# SQUIDCtrl_Rev2.net
KiCad netlist of a schematic drawn in Altium Designer
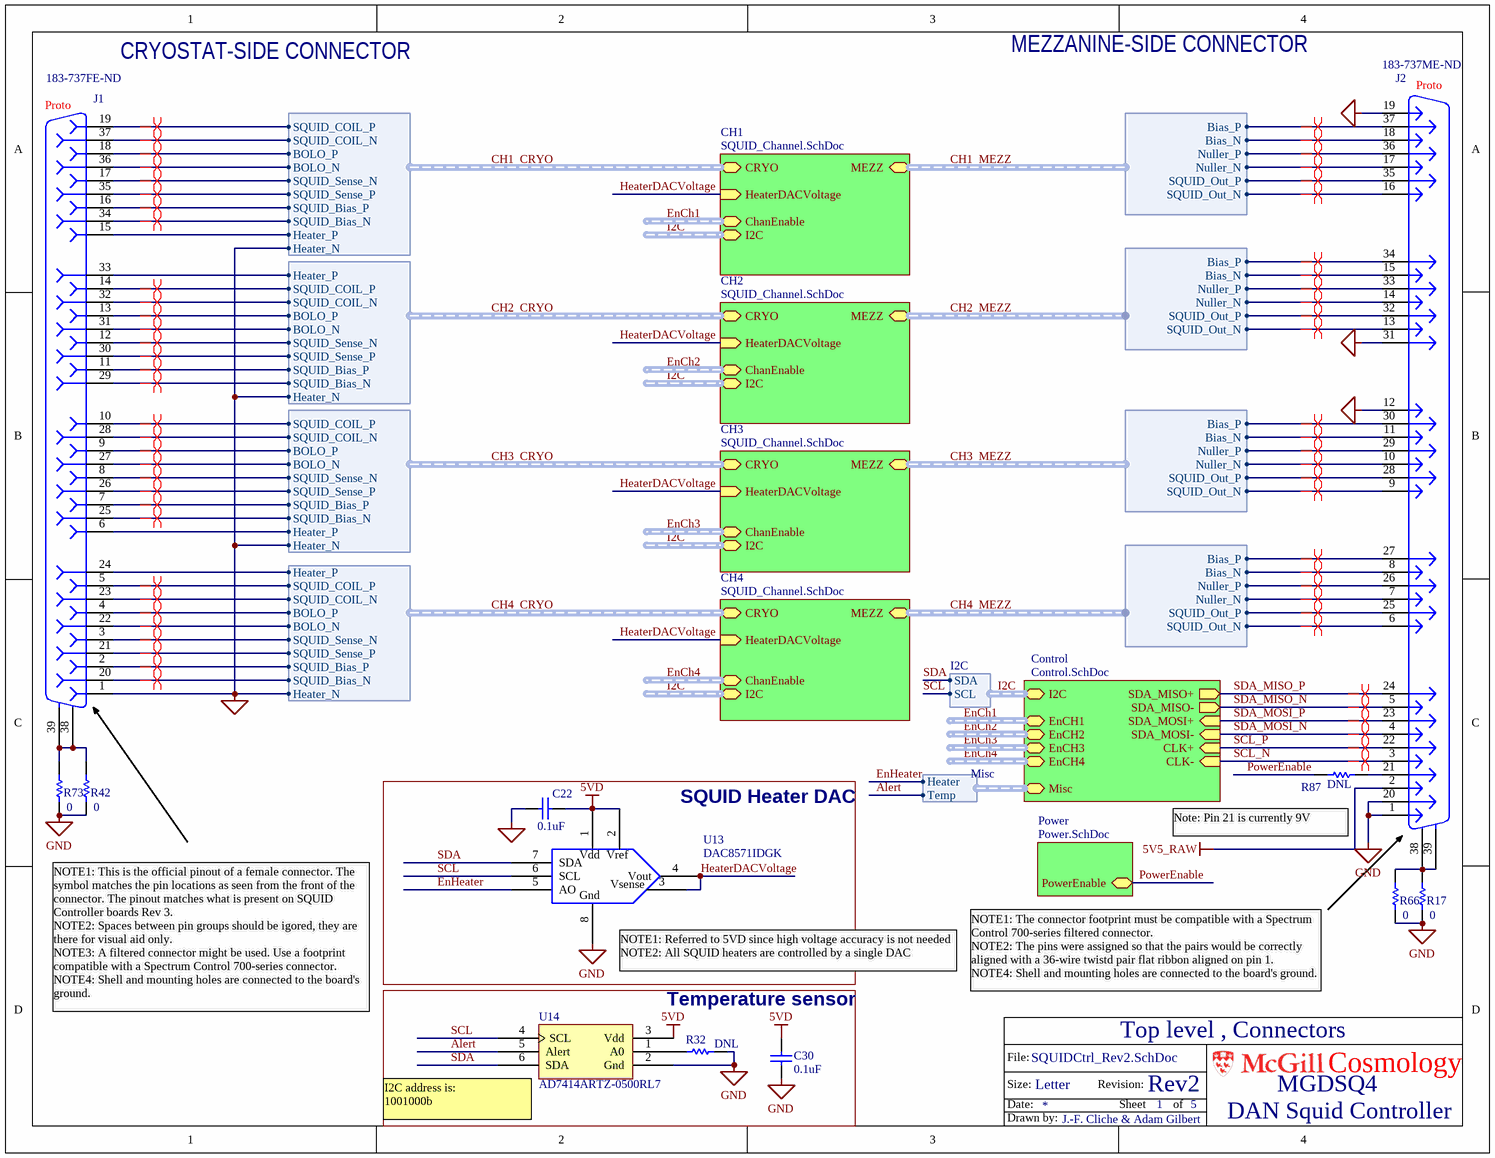
[diagram p0: SQUIDCtrl_Rev2.SchDoc]

(export (version "E")
  (design (tool "Eeschema 10.0.6"))
  (components
    (comp (ref "C22")
      (value "0.1uF")
      (footprint "0603")
      (description "Capacitor, Ceramic, 0603")
      (fields (field (name "MANUFACTURER") "Generic"))
      (libsource (lib "MiniSquidCtrl") (part "Cap0603"))
    )
    (comp (ref "C30")
      (value "0.1uF")
      (footprint "0603")
      (description "Capacitor, Ceramic, 0603")
      (fields (field (name "MANUFACTURER") "Generic"))
      (libsource (lib "MiniSquidCtrl") (part "Cap0603"))
    )
    (comp (ref "J1")
      (value "DB37F_Resize")
      (footprint "DSUB37-F (590mils)")
      (description "DB37F")
      (fields
        (field (name "MANUFACTURER") "Generic")
        (field (name "SYMBOL STATUS") "Proto")
        (field (name "SUPPLIER PART NUMBER 1") "183-737FE-ND")
      )
      (libsource (lib "MiniSquidCtrl") (part "DB37F_Resize"))
    )
    (comp (ref "J2")
      (value "DB37M_Resize")
      (footprint "DSUB37-M (590mils)")
      (description "DB37M")
      (fields
        (field (name "MANUFACTURER") "Generic")
        (field (name "SYMBOL STATUS") "Proto")
        (field (name "SUPPLIER PART NUMBER 1") "183-737ME-ND")
      )
      (libsource (lib "MiniSquidCtrl") (part "DB37M_Resize"))
    )
    (comp (ref "R17")
      (value "0")
      (footprint "0603")
      (description "RES 0603")
      (fields (field (name "MANUFACTURER") "Generic"))
      (libsource (lib "MiniSquidCtrl") (part "RES 0603"))
    )
    (comp (ref "R32")
      (value "DNL")
      (footprint "0603")
      (description "RES 0603")
      (fields (field (name "MANUFACTURER") "Generic"))
      (libsource (lib "MiniSquidCtrl") (part "Res0603"))
    )
    (comp (ref "R42")
      (value "0")
      (footprint "0603")
      (description "RES 0603")
      (fields (field (name "MANUFACTURER") "Generic"))
      (libsource (lib "MiniSquidCtrl") (part "RES 0603"))
    )
    (comp (ref "R66")
      (value "0")
      (footprint "0603")
      (description "RES 0603")
      (fields (field (name "MANUFACTURER") "Generic"))
      (libsource (lib "MiniSquidCtrl") (part "RES 0603"))
    )
    (comp (ref "R73")
      (value "0")
      (footprint "0603")
      (description "RES 0603")
      (fields (field (name "MANUFACTURER") "Generic"))
      (libsource (lib "MiniSquidCtrl") (part "RES 0603"))
    )
    (comp (ref "R87")
      (value "DNL")
      (footprint "0603")
      (description "RES 0603")
      (fields (field (name "MANUFACTURER") "Generic"))
      (libsource (lib "MiniSquidCtrl") (part "Res0603"))
    )
    (comp (ref "U13")
      (value "DAC8571IDGK")
      (footprint "MSOP-8")
      (description "IC DAC 16BIT I2C V-OUT LP 8-MSOP")
      (libsource (lib "MiniSquidCtrl") (part "DAC8571IDGKR"))
    )
    (comp (ref "U14")
      (value "AD7414ARTZ-0500RL7")
      (footprint "SOT23-6")
      (description "Digital Temperature Sensor, 11-Bit, +/-2 Degree Accurate")
      (fields (field (name "MANUFACTURER") "Analog Devices"))
      (libsource (lib "MiniSquidCtrl") (part "AD7414ARTZ-0500RL7"))
    )
  )
  (nets
    (net (code "16") (name "/Alert") (class "Default")
      (node (ref "U14") (pin "5") (pinfunction "Alert_5") (pintype "passive"))
    )
    (net (code "25") (name "/EnHeater") (class "Default")
      (node (ref "U13") (pin "5") (pinfunction "AO_5") (pintype "passive"))
    )
    (net (code "26") (name "/HeaterDACVoltage") (class "Default")
      (node (ref "U13") (pin "3") (pinfunction "Vsense_3") (pintype "passive"))
      (node (ref "U13") (pin "4") (pinfunction "Vout_4") (pintype "passive"))
    )
    (net (code "28") (name "/PowerEnable") (class "Default")
      (node (ref "R87") (pin "1") (pinfunction "1_1") (pintype "passive"))
    )
    (net (code "29") (name "/SCL") (class "Default")
      (node (ref "U13") (pin "6") (pinfunction "SCL_6") (pintype "passive"))
      (node (ref "U14") (pin "4") (pinfunction "SCL_4") (pintype "passive"))
    )
    (net (code "30") (name "/SCL_N") (class "Default")
      (node (ref "J2") (pin "3") (pinfunction "3_3") (pintype "passive"))
    )
    (net (code "31") (name "/SCL_P") (class "Default")
      (node (ref "J2") (pin "22") (pinfunction "22_22") (pintype "passive"))
    )
    (net (code "32") (name "/SDA") (class "Default")
      (node (ref "U13") (pin "7") (pinfunction "SDA_7") (pintype "passive"))
      (node (ref "U14") (pin "6") (pinfunction "SDA_6") (pintype "passive"))
    )
    (net (code "33") (name "/SDA_MISO_N") (class "Default")
      (node (ref "J2") (pin "5") (pinfunction "5_5") (pintype "passive"))
    )
    (net (code "34") (name "/SDA_MISO_P") (class "Default")
      (node (ref "J2") (pin "24") (pinfunction "24_24") (pintype "passive"))
    )
    (net (code "35") (name "/SDA_MOSI_N") (class "Default")
      (node (ref "J2") (pin "4") (pinfunction "4_4") (pintype "passive"))
    )
    (net (code "36") (name "/SDA_MOSI_P") (class "Default")
      (node (ref "J2") (pin "23") (pinfunction "23_23") (pintype "passive"))
    )
    (net (code "43") (name "5V5_RAW") (class "Default")
      (node (ref "J2") (pin "2") (pinfunction "2_2") (pintype "passive"))
    )
    (net (code "44") (name "5VD") (class "Default")
      (node (ref "C22") (pin "2") (pinfunction "2_2") (pintype "passive"))
      (node (ref "C30") (pin "2") (pinfunction "2_2") (pintype "passive"))
      (node (ref "U13") (pin "1") (pinfunction "Vdd_1") (pintype "passive"))
      (node (ref "U13") (pin "2") (pinfunction "Vref_2") (pintype "passive"))
      (node (ref "U14") (pin "3") (pinfunction "Vdd_3") (pintype "power_in"))
    )
    (net (code "45") (name "GND") (class "Default")
      (node (ref "C22") (pin "1") (pinfunction "1_1") (pintype "passive"))
      (node (ref "C30") (pin "1") (pinfunction "1_1") (pintype "passive"))
      (node (ref "J1") (pin "1") (pinfunction "1_1") (pintype "passive"))
      (node (ref "J2") (pin "1") (pinfunction "1_1") (pintype "passive"))
      (node (ref "J2") (pin "12") (pinfunction "12_12") (pintype "passive"))
      (node (ref "J2") (pin "19") (pinfunction "19_19") (pintype "passive"))
      (node (ref "J2") (pin "20") (pinfunction "20_20") (pintype "passive"))
      (node (ref "J2") (pin "31") (pinfunction "31_31") (pintype "passive"))
      (node (ref "R17") (pin "1") (pinfunction "1_1") (pintype "passive"))
      (node (ref "R32") (pin "2") (pinfunction "2_2") (pintype "passive"))
      (node (ref "R42") (pin "1") (pinfunction "1_1") (pintype "passive"))
      (node (ref "R66") (pin "1") (pinfunction "1_1") (pintype "passive"))
      (node (ref "R73") (pin "1") (pinfunction "1_1") (pintype "passive"))
      (node (ref "U13") (pin "8") (pinfunction "Gnd_8") (pintype "passive"))
      (node (ref "U14") (pin "2") (pinfunction "Gnd_2") (pintype "passive"))
    )
    (net (code "46") (name "Net-(J1-MH1)") (class "Default")
      (node (ref "J1") (pin "38") (pinfunction "MH1_38") (pintype "passive"))
      (node (ref "J1") (pin "39") (pinfunction "MH2_39") (pintype "passive"))
      (node (ref "R42") (pin "2") (pinfunction "2_2") (pintype "passive"))
      (node (ref "R73") (pin "2") (pinfunction "2_2") (pintype "passive"))
    )
    (net (code "47") (name "Net-(J2-MH1)") (class "Default")
      (node (ref "J2") (pin "38") (pinfunction "MH1_38") (pintype "passive"))
      (node (ref "J2") (pin "39") (pinfunction "MH2_39") (pintype "passive"))
      (node (ref "R17") (pin "2") (pinfunction "2_2") (pintype "passive"))
      (node (ref "R66") (pin "2") (pinfunction "2_2") (pintype "passive"))
    )
    (net (code "48") (name "Net-(J2-Pad21)") (class "Default")
      (node (ref "J2") (pin "21") (pinfunction "21_21") (pintype "passive"))
      (node (ref "R87") (pin "2") (pinfunction "2_2") (pintype "passive"))
    )
    (net (code "49") (name "Net-(U14-A0)") (class "Default")
      (node (ref "R32") (pin "1") (pinfunction "1_1") (pintype "passive"))
      (node (ref "U14") (pin "1") (pinfunction "A0_1") (pintype "power_in"))
    )
    (net (code "50") (name "unconnected-(J1-Pad2)") (class "Default")
      (node (ref "J1") (pin "2") (pinfunction "2_2") (pintype "passive"))
    )
    (net (code "51") (name "unconnected-(J1-Pad3)") (class "Default")
      (node (ref "J1") (pin "3") (pinfunction "3_3") (pintype "passive"))
    )
    (net (code "52") (name "unconnected-(J1-Pad4)") (class "Default")
      (node (ref "J1") (pin "4") (pinfunction "4_4") (pintype "passive"))
    )
    (net (code "53") (name "unconnected-(J1-Pad5)") (class "Default")
      (node (ref "J1") (pin "5") (pinfunction "5_5") (pintype "passive"))
    )
    (net (code "54") (name "unconnected-(J1-Pad6)") (class "Default")
      (node (ref "J1") (pin "6") (pinfunction "6_6") (pintype "passive"))
    )
    (net (code "55") (name "unconnected-(J1-Pad7)") (class "Default")
      (node (ref "J1") (pin "7") (pinfunction "7_7") (pintype "passive"))
    )
    (net (code "56") (name "unconnected-(J1-Pad8)") (class "Default")
      (node (ref "J1") (pin "8") (pinfunction "8_8") (pintype "passive"))
    )
    (net (code "57") (name "unconnected-(J1-Pad9)") (class "Default")
      (node (ref "J1") (pin "9") (pinfunction "9_9") (pintype "passive"))
    )
    (net (code "58") (name "unconnected-(J1-Pad10)") (class "Default")
      (node (ref "J1") (pin "10") (pinfunction "10_10") (pintype "passive"))
    )
    (net (code "59") (name "unconnected-(J1-Pad11)") (class "Default")
      (node (ref "J1") (pin "11") (pinfunction "11_11") (pintype "passive"))
    )
    (net (code "60") (name "unconnected-(J1-Pad12)") (class "Default")
      (node (ref "J1") (pin "12") (pinfunction "12_12") (pintype "passive"))
    )
    (net (code "61") (name "unconnected-(J1-Pad13)") (class "Default")
      (node (ref "J1") (pin "13") (pinfunction "13_13") (pintype "passive"))
    )
    (net (code "62") (name "unconnected-(J1-Pad14)") (class "Default")
      (node (ref "J1") (pin "14") (pinfunction "14_14") (pintype "passive"))
    )
    (net (code "63") (name "unconnected-(J1-Pad15)") (class "Default")
      (node (ref "J1") (pin "15") (pinfunction "15_15") (pintype "passive"))
    )
    (net (code "64") (name "unconnected-(J1-Pad16)") (class "Default")
      (node (ref "J1") (pin "16") (pinfunction "16_16") (pintype "passive"))
    )
    (net (code "65") (name "unconnected-(J1-Pad17)") (class "Default")
      (node (ref "J1") (pin "17") (pinfunction "17_17") (pintype "passive"))
    )
    (net (code "66") (name "unconnected-(J1-Pad18)") (class "Default")
      (node (ref "J1") (pin "18") (pinfunction "18_18") (pintype "passive"))
    )
    (net (code "67") (name "unconnected-(J1-Pad19)") (class "Default")
      (node (ref "J1") (pin "19") (pinfunction "19_19") (pintype "passive"))
    )
    (net (code "68") (name "unconnected-(J1-Pad20)") (class "Default")
      (node (ref "J1") (pin "20") (pinfunction "20_20") (pintype "passive"))
    )
    (net (code "69") (name "unconnected-(J1-Pad21)") (class "Default")
      (node (ref "J1") (pin "21") (pinfunction "21_21") (pintype "passive"))
    )
    (net (code "70") (name "unconnected-(J1-Pad22)") (class "Default")
      (node (ref "J1") (pin "22") (pinfunction "22_22") (pintype "passive"))
    )
    (net (code "71") (name "unconnected-(J1-Pad23)") (class "Default")
      (node (ref "J1") (pin "23") (pinfunction "23_23") (pintype "passive"))
    )
    (net (code "72") (name "unconnected-(J1-Pad24)") (class "Default")
      (node (ref "J1") (pin "24") (pinfunction "24_24") (pintype "passive"))
    )
    (net (code "73") (name "unconnected-(J1-Pad25)") (class "Default")
      (node (ref "J1") (pin "25") (pinfunction "25_25") (pintype "passive"))
    )
    (net (code "74") (name "unconnected-(J1-Pad26)") (class "Default")
      (node (ref "J1") (pin "26") (pinfunction "26_26") (pintype "passive"))
    )
    (net (code "75") (name "unconnected-(J1-Pad27)") (class "Default")
      (node (ref "J1") (pin "27") (pinfunction "27_27") (pintype "passive"))
    )
    (net (code "76") (name "unconnected-(J1-Pad28)") (class "Default")
      (node (ref "J1") (pin "28") (pinfunction "28_28") (pintype "passive"))
    )
    (net (code "77") (name "unconnected-(J1-Pad29)") (class "Default")
      (node (ref "J1") (pin "29") (pinfunction "29_29") (pintype "passive"))
    )
    (net (code "78") (name "unconnected-(J1-Pad30)") (class "Default")
      (node (ref "J1") (pin "30") (pinfunction "30_30") (pintype "passive"))
    )
    (net (code "79") (name "unconnected-(J1-Pad31)") (class "Default")
      (node (ref "J1") (pin "31") (pinfunction "31_31") (pintype "passive"))
    )
    (net (code "80") (name "unconnected-(J1-Pad32)") (class "Default")
      (node (ref "J1") (pin "32") (pinfunction "32_32") (pintype "passive"))
    )
    (net (code "81") (name "unconnected-(J1-Pad33)") (class "Default")
      (node (ref "J1") (pin "33") (pinfunction "33_33") (pintype "passive"))
    )
    (net (code "82") (name "unconnected-(J1-Pad34)") (class "Default")
      (node (ref "J1") (pin "34") (pinfunction "34_34") (pintype "passive"))
    )
    (net (code "83") (name "unconnected-(J1-Pad35)") (class "Default")
      (node (ref "J1") (pin "35") (pinfunction "35_35") (pintype "passive"))
    )
    (net (code "84") (name "unconnected-(J1-Pad36)") (class "Default")
      (node (ref "J1") (pin "36") (pinfunction "36_36") (pintype "passive"))
    )
    (net (code "85") (name "unconnected-(J1-Pad37)") (class "Default")
      (node (ref "J1") (pin "37") (pinfunction "37_37") (pintype "passive"))
    )
    (net (code "86") (name "unconnected-(J2-Pad6)") (class "Default")
      (node (ref "J2") (pin "6") (pinfunction "6_6") (pintype "passive"))
    )
    (net (code "87") (name "unconnected-(J2-Pad7)") (class "Default")
      (node (ref "J2") (pin "7") (pinfunction "7_7") (pintype "passive"))
    )
    (net (code "88") (name "unconnected-(J2-Pad8)") (class "Default")
      (node (ref "J2") (pin "8") (pinfunction "8_8") (pintype "passive"))
    )
    (net (code "89") (name "unconnected-(J2-Pad9)") (class "Default")
      (node (ref "J2") (pin "9") (pinfunction "9_9") (pintype "passive"))
    )
    (net (code "90") (name "unconnected-(J2-Pad10)") (class "Default")
      (node (ref "J2") (pin "10") (pinfunction "10_10") (pintype "passive"))
    )
    (net (code "91") (name "unconnected-(J2-Pad11)") (class "Default")
      (node (ref "J2") (pin "11") (pinfunction "11_11") (pintype "passive"))
    )
    (net (code "92") (name "unconnected-(J2-Pad13)") (class "Default")
      (node (ref "J2") (pin "13") (pinfunction "13_13") (pintype "passive"))
    )
    (net (code "93") (name "unconnected-(J2-Pad14)") (class "Default")
      (node (ref "J2") (pin "14") (pinfunction "14_14") (pintype "passive"))
    )
    (net (code "94") (name "unconnected-(J2-Pad15)") (class "Default")
      (node (ref "J2") (pin "15") (pinfunction "15_15") (pintype "passive"))
    )
    (net (code "95") (name "unconnected-(J2-Pad16)") (class "Default")
      (node (ref "J2") (pin "16") (pinfunction "16_16") (pintype "passive"))
    )
    (net (code "96") (name "unconnected-(J2-Pad17)") (class "Default")
      (node (ref "J2") (pin "17") (pinfunction "17_17") (pintype "passive"))
    )
    (net (code "97") (name "unconnected-(J2-Pad18)") (class "Default")
      (node (ref "J2") (pin "18") (pinfunction "18_18") (pintype "passive"))
    )
    (net (code "98") (name "unconnected-(J2-Pad25)") (class "Default")
      (node (ref "J2") (pin "25") (pinfunction "25_25") (pintype "passive"))
    )
    (net (code "99") (name "unconnected-(J2-Pad26)") (class "Default")
      (node (ref "J2") (pin "26") (pinfunction "26_26") (pintype "passive"))
    )
    (net (code "100") (name "unconnected-(J2-Pad27)") (class "Default")
      (node (ref "J2") (pin "27") (pinfunction "27_27") (pintype "passive"))
    )
    (net (code "101") (name "unconnected-(J2-Pad28)") (class "Default")
      (node (ref "J2") (pin "28") (pinfunction "28_28") (pintype "passive"))
    )
    (net (code "102") (name "unconnected-(J2-Pad29)") (class "Default")
      (node (ref "J2") (pin "29") (pinfunction "29_29") (pintype "passive"))
    )
    (net (code "103") (name "unconnected-(J2-Pad30)") (class "Default")
      (node (ref "J2") (pin "30") (pinfunction "30_30") (pintype "passive"))
    )
    (net (code "104") (name "unconnected-(J2-Pad32)") (class "Default")
      (node (ref "J2") (pin "32") (pinfunction "32_32") (pintype "passive"))
    )
    (net (code "105") (name "unconnected-(J2-Pad33)") (class "Default")
      (node (ref "J2") (pin "33") (pinfunction "33_33") (pintype "passive"))
    )
    (net (code "106") (name "unconnected-(J2-Pad34)") (class "Default")
      (node (ref "J2") (pin "34") (pinfunction "34_34") (pintype "passive"))
    )
    (net (code "107") (name "unconnected-(J2-Pad35)") (class "Default")
      (node (ref "J2") (pin "35") (pinfunction "35_35") (pintype "passive"))
    )
    (net (code "108") (name "unconnected-(J2-Pad36)") (class "Default")
      (node (ref "J2") (pin "36") (pinfunction "36_36") (pintype "passive"))
    )
    (net (code "109") (name "unconnected-(J2-Pad37)") (class "Default")
      (node (ref "J2") (pin "37") (pinfunction "37_37") (pintype "passive"))
    )
  )
)
